# 5V_Outputs.net
KiCad netlist of a schematic drawn in Altium Designer
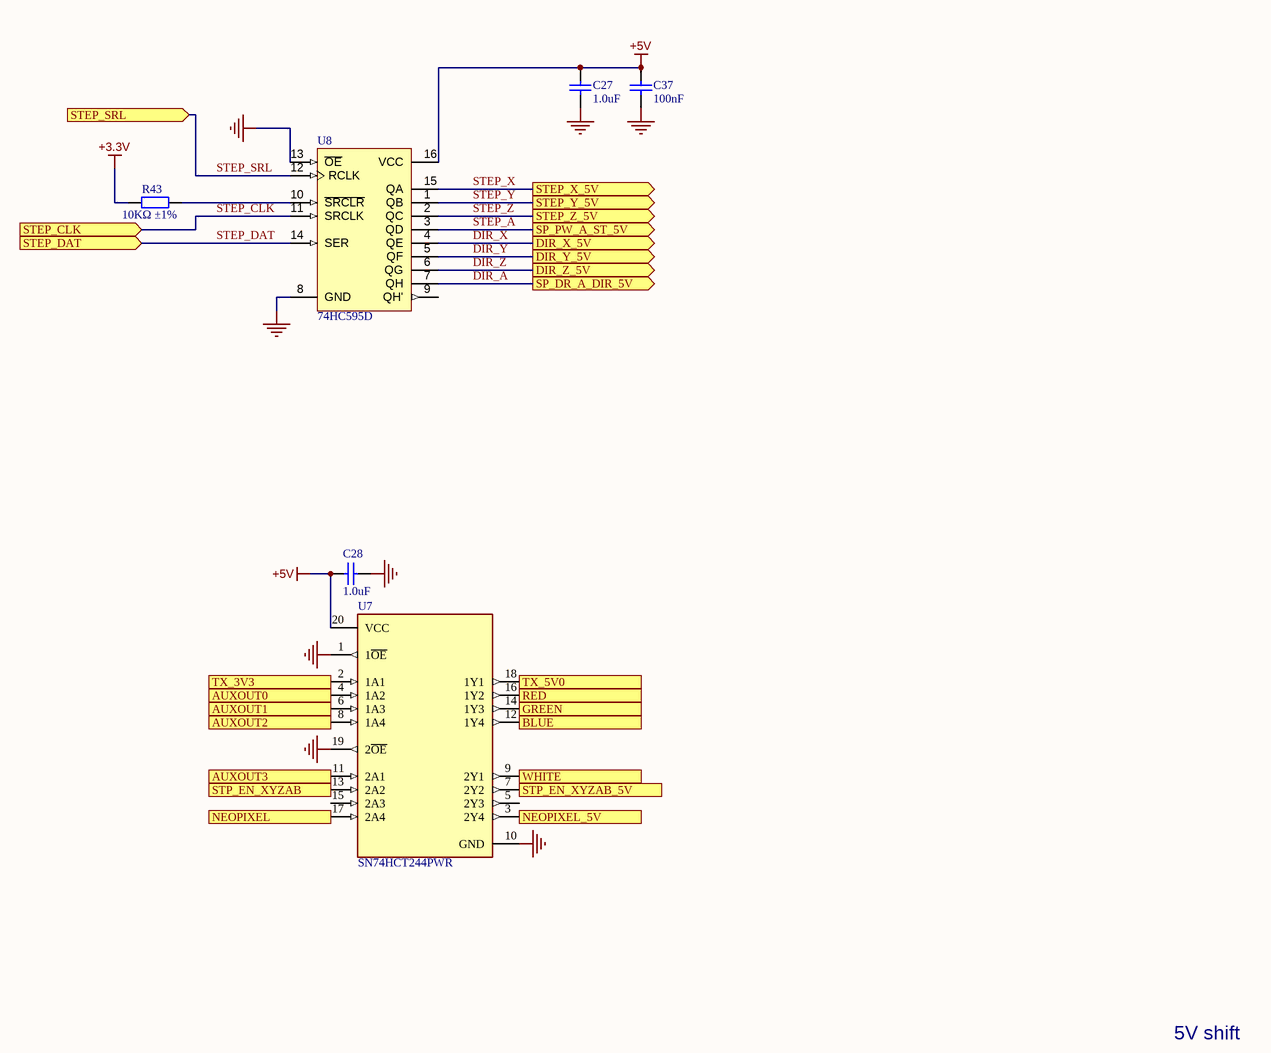
[diagram p0: 5V_Outputs.SchDoc]

(export (version "E")
  (design (tool "Eeschema 10.0.6"))
  (components
    (comp (ref "C27")
      (value "1.0uF")
      (footprint "0402_C")
      (description "Chip capacitor")
      (fields
        (field (name "MANUFACTURER") "Samsung Electro-Mechanics")
        (field (name "PARTNUMBER") "CL05A105KA5NQNC")
      )
      (libsource (lib "Cap") (part "0402 1.0uF (105) 10% 25V"))
    )
    (comp (ref "C28")
      (value "1.0uF")
      (footprint "0402_C")
      (description "Chip capacitor")
      (fields
        (field (name "MANUFACTURER") "Samsung Electro-Mechanics")
        (field (name "PARTNUMBER") "CL05A105KA5NQNC")
      )
      (libsource (lib "Cap") (part "0402 1.0uF (105) 10% 25V"))
    )
    (comp (ref "C37")
      (value "100nF")
      (footprint "0402_C")
      (description "Chip capacitors")
      (fields
        (field (name "MANUFACTURER") "Samsung Electro-Mechanics")
        (field (name "PARTNUMBER") "CL05B104KO5NNNC")
      )
      (libsource (lib "Cap") (part "0402 100nF (104) 10% 16V"))
    )
    (comp (ref "R43")
      (value "10KΩ ±1%")
      (footprint "0402_R")
      (description "Chip resistor")
      (fields (field (name "MANUFACTURER") "Uniroyal Elec") (field (name "PARTNUMBER") "0402WGF1002TCE"))
      (libsource (lib "PrintNC_GRBLHAL_Breakout") (part "0402 10K (1002) 1%"))
    )
    (comp (ref "U7")
      (value "SN74HCT244PWR")
      (footprint "FP-PW0020A-IPC_B")
      (description "IC BUF NON-INVERT 5.5V 20TSSOP")
      (libsource (lib "Altium Content Vault") (part "70bec8925b4a748e1281c287d5e2f08"))
    )
    (comp (ref "U8")
      (value "74HC595D")
      (footprint "SOIC-16_150mil")
      (description "8 bit serial in or parallel out shift register")
      (libsource (lib "IC") (part "74HC595D_[C5947]"))
    )
  )
  (nets
    (net (code "1") (name "+3.3V") (class "Default")
      (node (ref "R43") (pin "2") (pinfunction "2_2") (pintype "passive"))
    )
    (net (code "2") (name "+5V") (class "Default")
      (node (ref "C27") (pin "2") (pinfunction "2_2") (pintype "passive"))
      (node (ref "C28") (pin "1") (pinfunction "1_1") (pintype "passive"))
      (node (ref "C37") (pin "2") (pinfunction "2_2") (pintype "passive"))
      (node (ref "U7") (pin "20") (pinfunction "VCC_20") (pintype "power_in"))
      (node (ref "U8") (pin "16") (pinfunction "VCC_16") (pintype "power_in"))
    )
    (net (code "3") (name "/AUXOUT0") (class "Default")
      (node (ref "U7") (pin "4") (pinfunction "1A2_4") (pintype "input"))
    )
    (net (code "4") (name "/AUXOUT1") (class "Default")
      (node (ref "U7") (pin "6") (pinfunction "1A3_6") (pintype "input"))
    )
    (net (code "5") (name "/AUXOUT2") (class "Default")
      (node (ref "U7") (pin "8") (pinfunction "1A4_8") (pintype "input"))
    )
    (net (code "6") (name "/AUXOUT3") (class "Default")
      (node (ref "U7") (pin "11") (pinfunction "2A1_11") (pintype "input"))
    )
    (net (code "7") (name "/BLUE") (class "Default")
      (node (ref "U7") (pin "12") (pinfunction "1Y4_12") (pintype "output"))
    )
    (net (code "8") (name "/DIR_A") (class "Default")
      (node (ref "U8") (pin "7") (pinfunction "QH_7") (pintype "tri_state"))
    )
    (net (code "9") (name "/DIR_X") (class "Default")
      (node (ref "U8") (pin "4") (pinfunction "QE_4") (pintype "tri_state"))
    )
    (net (code "10") (name "/DIR_Y") (class "Default")
      (node (ref "U8") (pin "5") (pinfunction "QF_5") (pintype "tri_state"))
    )
    (net (code "11") (name "/DIR_Z") (class "Default")
      (node (ref "U8") (pin "6") (pinfunction "QG_6") (pintype "tri_state"))
    )
    (net (code "12") (name "/GREEN") (class "Default")
      (node (ref "U7") (pin "14") (pinfunction "1Y3_14") (pintype "output"))
    )
    (net (code "13") (name "/NEOPIXEL") (class "Default")
      (node (ref "U7") (pin "17") (pinfunction "2A4_17") (pintype "input"))
    )
    (net (code "14") (name "/NEOPIXEL_5V") (class "Default")
      (node (ref "U7") (pin "3") (pinfunction "2Y4_3") (pintype "output"))
    )
    (net (code "15") (name "/RED") (class "Default")
      (node (ref "U7") (pin "16") (pinfunction "1Y2_16") (pintype "output"))
    )
    (net (code "16") (name "/STEP_A") (class "Default")
      (node (ref "U8") (pin "3") (pinfunction "QD_3") (pintype "tri_state"))
    )
    (net (code "17") (name "/STEP_CLK") (class "Default")
      (node (ref "U8") (pin "11") (pinfunction "SRCLK_11") (pintype "input"))
    )
    (net (code "18") (name "/STEP_DAT") (class "Default")
      (node (ref "U8") (pin "14") (pinfunction "SER_14") (pintype "input"))
    )
    (net (code "19") (name "/STEP_SRL") (class "Default")
      (node (ref "U8") (pin "12") (pinfunction "RCLK_12") (pintype "input"))
    )
    (net (code "20") (name "/STEP_X") (class "Default")
      (node (ref "U8") (pin "15") (pinfunction "QA_15") (pintype "tri_state"))
    )
    (net (code "21") (name "/STEP_Y") (class "Default")
      (node (ref "U8") (pin "1") (pinfunction "QB_1") (pintype "tri_state"))
    )
    (net (code "22") (name "/STEP_Z") (class "Default")
      (node (ref "U8") (pin "2") (pinfunction "QC_2") (pintype "tri_state"))
    )
    (net (code "23") (name "/STP_EN_XYZAB") (class "Default")
      (node (ref "U7") (pin "13") (pinfunction "2A2_13") (pintype "input"))
    )
    (net (code "24") (name "/STP_EN_XYZAB_5V") (class "Default")
      (node (ref "U7") (pin "7") (pinfunction "2Y2_7") (pintype "output"))
    )
    (net (code "25") (name "/TX_3V3") (class "Default")
      (node (ref "U7") (pin "2") (pinfunction "1A1_2") (pintype "input"))
    )
    (net (code "26") (name "/TX_5V0") (class "Default")
      (node (ref "U7") (pin "18") (pinfunction "1Y1_18") (pintype "output"))
    )
    (net (code "27") (name "/WHITE") (class "Default")
      (node (ref "U7") (pin "9") (pinfunction "2Y1_9") (pintype "output"))
    )
    (net (code "28") (name "GND") (class "Default")
      (node (ref "C27") (pin "1") (pinfunction "1_1") (pintype "passive"))
      (node (ref "C28") (pin "2") (pinfunction "2_2") (pintype "passive"))
      (node (ref "C37") (pin "1") (pinfunction "1_1") (pintype "passive"))
      (node (ref "U7") (pin "1") (pinfunction "1~{OE}_1") (pintype "output"))
      (node (ref "U7") (pin "10") (pinfunction "GND_10") (pintype "power_in"))
      (node (ref "U7") (pin "19") (pinfunction "2~{OE}_19") (pintype "output"))
      (node (ref "U8") (pin "13") (pinfunction "~{OE}_13") (pintype "input"))
      (node (ref "U8") (pin "8") (pinfunction "GND_8") (pintype "power_in"))
    )
    (net (code "29") (name "Net-(U8-~{SRCLR})") (class "Default")
      (node (ref "R43") (pin "1") (pinfunction "1_1") (pintype "passive"))
      (node (ref "U8") (pin "10") (pinfunction "~{SRCLR}_10") (pintype "input"))
    )
    (net (code "30") (name "unconnected-(U7-2A3-Pad15)") (class "Default")
      (node (ref "U7") (pin "15") (pinfunction "2A3_15") (pintype "input"))
    )
    (net (code "31") (name "unconnected-(U7-2Y3-Pad5)") (class "Default")
      (node (ref "U7") (pin "5") (pinfunction "2Y3_5") (pintype "output"))
    )
    (net (code "32") (name "unconnected-(U8-QH'-Pad9)") (class "Default")
      (node (ref "U8") (pin "9") (pinfunction "QH'_9") (pintype "output"))
    )
  )
)
